# MOTOR_DRV.net
KiCad netlist of a schematic drawn in Altium Designer
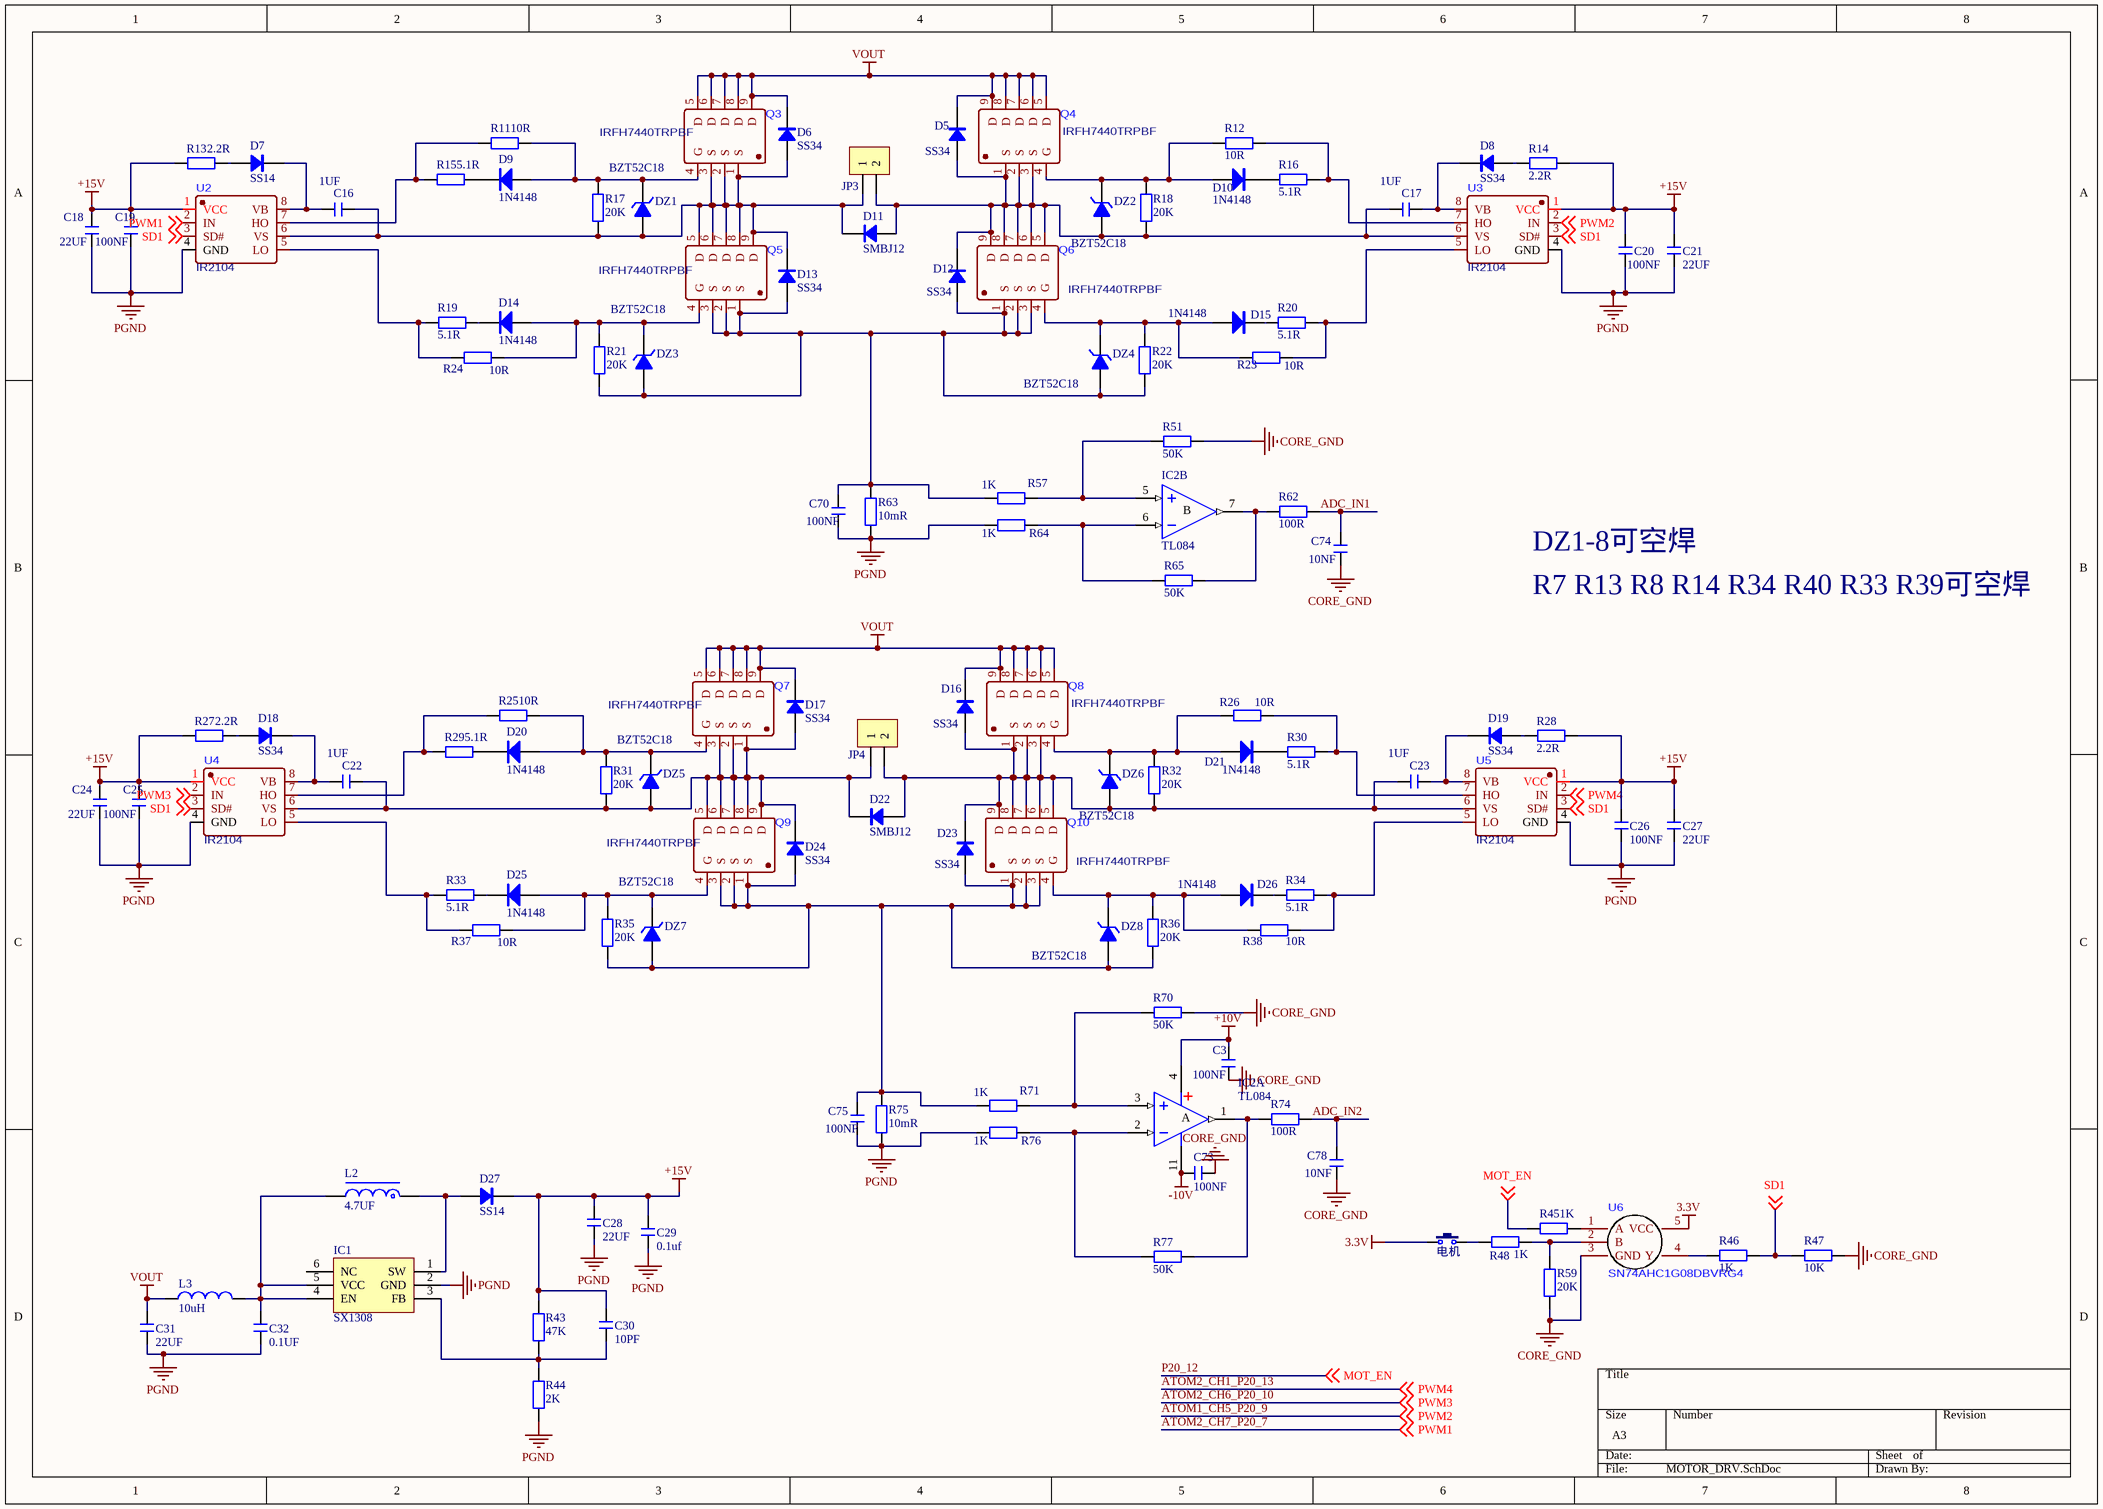
[diagram p0: MOTOR_DRV.SchDoc]

(export (version "E")
  (design (tool "Eeschema 10.0.6"))
  (components
    (comp (ref "C3")
      (value "100NF")
      (footprint "C 0805_L")
      (description "无极性贴片电容")
      (fields (field (name "版权归属") "源创客"))
      (libsource (lib "3.1   - 电阻-电容-电感") (part "C"))
    )
    (comp (ref "C16")
      (value "1UF")
      (footprint "C 1206_L")
      (description "无极性贴片电容")
      (fields (field (name "版权归属") "源创客"))
      (libsource (lib "3.1   - 电阻-电容-电感") (part "C"))
    )
    (comp (ref "C17")
      (value "1UF")
      (footprint "C 1206_L")
      (description "无极性贴片电容")
      (fields (field (name "版权归属") "源创客"))
      (libsource (lib "3.1   - 电阻-电容-电感") (part "C"))
    )
    (comp (ref "C18")
      (value "22UF")
      (footprint "C 0805_L")
      (description "无极性贴片电容")
      (fields (field (name "版权归属") "源创客"))
      (libsource (lib "3.1   - 电阻-电容-电感") (part "C"))
    )
    (comp (ref "C19")
      (value "100NF")
      (footprint "C 0805_L")
      (description "无极性贴片电容")
      (fields (field (name "版权归属") "源创客"))
      (libsource (lib "3.1   - 电阻-电容-电感") (part "C"))
    )
    (comp (ref "C20")
      (value "100NF")
      (footprint "C 0805_L")
      (description "无极性贴片电容")
      (fields (field (name "版权归属") "源创客"))
      (libsource (lib "3.1   - 电阻-电容-电感") (part "C"))
    )
    (comp (ref "C21")
      (value "22UF")
      (footprint "C 0805_L")
      (description "无极性贴片电容")
      (fields (field (name "版权归属") "源创客"))
      (libsource (lib "3.1   - 电阻-电容-电感") (part "C"))
    )
    (comp (ref "C22")
      (value "1UF")
      (footprint "C 1206_L")
      (description "无极性贴片电容")
      (fields (field (name "版权归属") "源创客"))
      (libsource (lib "3.1   - 电阻-电容-电感") (part "C"))
    )
    (comp (ref "C23")
      (value "1UF")
      (footprint "C 1206_L")
      (description "无极性贴片电容")
      (fields (field (name "版权归属") "源创客"))
      (libsource (lib "3.1   - 电阻-电容-电感") (part "C"))
    )
    (comp (ref "C24")
      (value "22UF")
      (footprint "C 0805_L")
      (description "无极性贴片电容")
      (fields (field (name "版权归属") "源创客"))
      (libsource (lib "3.1   - 电阻-电容-电感") (part "C"))
    )
    (comp (ref "C25")
      (value "100NF")
      (footprint "C 0805_L")
      (description "无极性贴片电容")
      (fields (field (name "版权归属") "源创客"))
      (libsource (lib "3.1   - 电阻-电容-电感") (part "C"))
    )
    (comp (ref "C26")
      (value "100NF")
      (footprint "C 0805_L")
      (description "无极性贴片电容")
      (fields (field (name "版权归属") "源创客"))
      (libsource (lib "3.1   - 电阻-电容-电感") (part "C"))
    )
    (comp (ref "C27")
      (value "22UF")
      (footprint "C 0805_L")
      (description "无极性贴片电容")
      (fields (field (name "版权归属") "源创客"))
      (libsource (lib "3.1   - 电阻-电容-电感") (part "C"))
    )
    (comp (ref "C28")
      (value "22UF")
      (footprint "C 1206_L")
      (description "无极性贴片电容")
      (fields (field (name "版权归属") "源创客"))
      (libsource (lib "3.1   - 电阻-电容-电感") (part "C"))
    )
    (comp (ref "C29")
      (value "0.1uf")
      (footprint "C 0805_L")
      (description "无极性贴片电容")
      (fields (field (name "版权归属") "源创客"))
      (libsource (lib "3.1   - 电阻-电容-电感") (part "C"))
    )
    (comp (ref "C30")
      (value "10PF")
      (footprint "C 0603_L")
      (description "无极性贴片电容")
      (fields (field (name "版权归属") "源创客"))
      (libsource (lib "3.1   - 电阻-电容-电感") (part "C"))
    )
    (comp (ref "C31")
      (value "22UF")
      (footprint "C 1206_L")
      (description "无极性贴片电容")
      (fields (field (name "版权归属") "源创客"))
      (libsource (lib "3.1   - 电阻-电容-电感") (part "C"))
    )
    (comp (ref "C32")
      (value "0.1UF")
      (footprint "C 0805_L")
      (description "无极性贴片电容")
      (fields (field (name "版权归属") "源创客"))
      (libsource (lib "3.1   - 电阻-电容-电感") (part "C"))
    )
    (comp (ref "C70")
      (value "100NF")
      (footprint "C 0805_L")
      (description "无极性贴片电容")
      (fields (field (name "版权归属") "源创客"))
      (libsource (lib "3.1   - 电阻-电容-电感") (part "C"))
    )
    (comp (ref "C73")
      (value "100NF")
      (footprint "C 0805_L")
      (description "无极性贴片电容")
      (fields (field (name "版权归属") "源创客"))
      (libsource (lib "3.1   - 电阻-电容-电感") (part "C"))
    )
    (comp (ref "C74")
      (value "10NF")
      (footprint "C 0805_L")
      (description "无极性贴片电容")
      (fields (field (name "版权归属") "源创客"))
      (libsource (lib "3.1   - 电阻-电容-电感") (part "C"))
    )
    (comp (ref "C75")
      (value "100NF")
      (footprint "C 0805_L")
      (description "无极性贴片电容")
      (fields (field (name "版权归属") "源创客"))
      (libsource (lib "3.1   - 电阻-电容-电感") (part "C"))
    )
    (comp (ref "C78")
      (value "10NF")
      (footprint "C 0805_L")
      (description "无极性贴片电容")
      (fields (field (name "版权归属") "源创客"))
      (libsource (lib "3.1   - 电阻-电容-电感") (part "C"))
    )
    (comp (ref "D5")
      (value "SS34")
      (footprint "SMA")
      (description "肖特基二极管")
      (fields (field (name "版权归属") "源创客"))
      (libsource (lib "8.1   - 二极管-整流桥") (part "SS34"))
    )
    (comp (ref "D6")
      (value "SS34")
      (footprint "SMA")
      (description "肖特基二极管")
      (fields (field (name "版权归属") "源创客"))
      (libsource (lib "8.1   - 二极管-整流桥") (part "SS34"))
    )
    (comp (ref "D7")
      (value "SS14")
      (footprint "SOD-123")
      (description "肖特基二极管")
      (fields (field (name "版权归属") "源创客"))
      (libsource (lib "8.1   - 二极管-整流桥") (part "SS34"))
    )
    (comp (ref "D8")
      (value "SS34")
      (footprint "SOD-123")
      (description "肖特基二极管")
      (fields (field (name "版权归属") "源创客"))
      (libsource (lib "8.1   - 二极管-整流桥") (part "SS34"))
    )
    (comp (ref "D9")
      (value "1N4148")
      (footprint "SOD-323")
      (description "高速开关二极管")
      (fields (field (name "版权归属") "源创客"))
      (libsource (lib "8.1   - 二极管-整流桥") (part "1N4148"))
    )
    (comp (ref "D10")
      (value "1N4148")
      (footprint "SOD-323")
      (description "高速开关二极管")
      (fields (field (name "版权归属") "源创客"))
      (libsource (lib "8.1   - 二极管-整流桥") (part "1N4148"))
    )
    (comp (ref "D11")
      (value "SMBJ12")
      (footprint "SMA")
      (description "肖特基二极管")
      (fields (field (name "版权归属") "源创客"))
      (libsource (lib "8.1   - 二极管-整流桥") (part "SS34"))
    )
    (comp (ref "D12")
      (value "SS34")
      (footprint "SMA")
      (description "肖特基二极管")
      (fields (field (name "版权归属") "源创客"))
      (libsource (lib "8.1   - 二极管-整流桥") (part "SS34"))
    )
    (comp (ref "D13")
      (value "SS34")
      (footprint "SMA")
      (description "肖特基二极管")
      (fields (field (name "版权归属") "源创客"))
      (libsource (lib "8.1   - 二极管-整流桥") (part "SS34"))
    )
    (comp (ref "D14")
      (value "1N4148")
      (footprint "SOD-323")
      (description "高速开关二极管")
      (fields (field (name "版权归属") "源创客"))
      (libsource (lib "8.1   - 二极管-整流桥") (part "1N4148"))
    )
    (comp (ref "D15")
      (value "1N4148")
      (footprint "SOD-323")
      (description "高速开关二极管")
      (fields (field (name "版权归属") "源创客"))
      (libsource (lib "8.1   - 二极管-整流桥") (part "1N4148"))
    )
    (comp (ref "D16")
      (value "SS34")
      (footprint "SMA")
      (description "肖特基二极管")
      (fields (field (name "版权归属") "源创客"))
      (libsource (lib "8.1   - 二极管-整流桥") (part "SS34"))
    )
    (comp (ref "D17")
      (value "SS34")
      (footprint "SMA")
      (description "肖特基二极管")
      (fields (field (name "版权归属") "源创客"))
      (libsource (lib "8.1   - 二极管-整流桥") (part "SS34"))
    )
    (comp (ref "D18")
      (value "SS34")
      (footprint "SOD-123")
      (description "肖特基二极管")
      (fields (field (name "版权归属") "源创客"))
      (libsource (lib "8.1   - 二极管-整流桥") (part "SS34"))
    )
    (comp (ref "D19")
      (value "SS34")
      (footprint "SOD-123")
      (description "肖特基二极管")
      (fields (field (name "版权归属") "源创客"))
      (libsource (lib "8.1   - 二极管-整流桥") (part "SS34"))
    )
    (comp (ref "D20")
      (value "1N4148")
      (footprint "SOD-323")
      (description "高速开关二极管")
      (fields (field (name "版权归属") "源创客"))
      (libsource (lib "8.1   - 二极管-整流桥") (part "1N4148"))
    )
    (comp (ref "D21")
      (value "1N4148")
      (footprint "SOD-323")
      (description "高速开关二极管")
      (fields (field (name "版权归属") "源创客"))
      (libsource (lib "8.1   - 二极管-整流桥") (part "1N4148"))
    )
    (comp (ref "D22")
      (value "SMBJ12")
      (footprint "SMA")
      (description "肖特基二极管")
      (fields (field (name "版权归属") "源创客"))
      (libsource (lib "8.1   - 二极管-整流桥") (part "SS34"))
    )
    (comp (ref "D23")
      (value "SS34")
      (footprint "SMA")
      (description "肖特基二极管")
      (fields (field (name "版权归属") "源创客"))
      (libsource (lib "8.1   - 二极管-整流桥") (part "SS34"))
    )
    (comp (ref "D24")
      (value "SS34")
      (footprint "SMA")
      (description "肖特基二极管")
      (fields (field (name "版权归属") "源创客"))
      (libsource (lib "8.1   - 二极管-整流桥") (part "SS34"))
    )
    (comp (ref "D25")
      (value "1N4148")
      (footprint "SOD-323")
      (description "高速开关二极管")
      (fields (field (name "版权归属") "源创客"))
      (libsource (lib "8.1   - 二极管-整流桥") (part "1N4148"))
    )
    (comp (ref "D26")
      (value "1N4148")
      (footprint "SOD-323")
      (description "高速开关二极管")
      (fields (field (name "版权归属") "源创客"))
      (libsource (lib "8.1   - 二极管-整流桥") (part "1N4148"))
    )
    (comp (ref "D27")
      (value "SS14")
      (footprint "SOD-123")
      (description "肖特基二极管")
      (fields (field (name "版权归属") "源创客"))
      (libsource (lib "8.1   - 二极管-整流桥") (part "SS24"))
    )
    (comp (ref "DZ1")
      (value "BZT52C18")
      (footprint "SOD-323")
      (description "18V稳压管")
      (fields (field (name "版权归属") "源创客"))
      (libsource (lib "8.1   - 二极管-整流桥") (part "1N4102"))
    )
    (comp (ref "DZ2")
      (value "BZT52C18")
      (footprint "SOD-323")
      (description "18V稳压管")
      (fields (field (name "版权归属") "源创客"))
      (libsource (lib "8.1   - 二极管-整流桥") (part "1N4102"))
    )
    (comp (ref "DZ3")
      (value "BZT52C18")
      (footprint "SOD-323")
      (description "18V稳压管")
      (fields (field (name "版权归属") "源创客"))
      (libsource (lib "8.1   - 二极管-整流桥") (part "1N4102"))
    )
    (comp (ref "DZ4")
      (value "BZT52C18")
      (footprint "SOD-323")
      (description "18V稳压管")
      (fields (field (name "版权归属") "源创客"))
      (libsource (lib "8.1   - 二极管-整流桥") (part "1N4102"))
    )
    (comp (ref "DZ5")
      (value "BZT52C18")
      (footprint "SOD-323")
      (description "18V稳压管")
      (fields (field (name "版权归属") "源创客"))
      (libsource (lib "8.1   - 二极管-整流桥") (part "1N4102"))
    )
    (comp (ref "DZ6")
      (value "BZT52C18")
      (footprint "SOD-323")
      (description "18V稳压管")
      (fields (field (name "版权归属") "源创客"))
      (libsource (lib "8.1   - 二极管-整流桥") (part "1N4102"))
    )
    (comp (ref "DZ7")
      (value "BZT52C18")
      (footprint "SOD-323")
      (description "18V稳压管")
      (fields (field (name "版权归属") "源创客"))
      (libsource (lib "8.1   - 二极管-整流桥") (part "1N4102"))
    )
    (comp (ref "DZ8")
      (value "BZT52C18")
      (footprint "SOD-323")
      (description "18V稳压管")
      (fields (field (name "版权归属") "源创客"))
      (libsource (lib "8.1   - 二极管-整流桥") (part "1N4102"))
    )
    (comp (ref "IC1")
      (value "SX1308")
      (footprint "SOT23-6N")
      (description "可调升压芯片")
      (fields (field (name "版权归属") "源创客"))
      (libsource (lib "1.3   - 电源类芯片") (part "SX1308"))
    )
    (comp (ref "IC2")
      (value "TL084")
      (footprint "SOP14_N")
      (description "4路运放")
      (fields (field (name "版权归属") "源创客"))
      (libsource (lib "1.5   - 运放-功放") (part "TL084"))
    )
    (comp (ref "JP3")
      (value "HDR-1X2")
      (footprint "KF2EDGK5.08-LI-2P")
      (description "2P接插件")
      (fields (field (name "版权归属") "源创客"))
      (libsource (lib "4.11 - 接插件-脚距5.08") (part "Header 2"))
    )
    (comp (ref "JP4")
      (value "HDR-1X2")
      (footprint "KF2EDGK5.08-LI-2P")
      (description "2P接插件")
      (fields (field (name "版权归属") "源创客"))
      (libsource (lib "4.11 - 接插件-脚距5.08") (part "Header 2"))
    )
    (comp (ref "L2")
      (value "4.7UF")
      (footprint "L-SMD-0420")
      (description "功率屏蔽电感")
      (fields (field (name "版权归属") "源创客"))
      (libsource (lib "3.1   - 电阻-电容-电感") (part "L-CDRH"))
    )
    (comp (ref "L3")
      (value "10uH")
      (footprint "L 0805_L")
      (description "小功率贴片电感")
      (fields (field (name "版权归属") "源创客"))
      (libsource (lib "3.1   - 电阻-电容-电感") (part "L"))
    )
    (comp (ref "Q3")
      (value "IRFH7440TRPBF")
      (footprint "PQFN-8P_L5.8-W4.9-P1.27-LS6.0-BL")
      (libsource (lib "IRFH7440TRPBF") (part "IRFH7440TRPBF"))
    )
    (comp (ref "Q4")
      (value "IRFH7440TRPBF")
      (footprint "PQFN-8P_L5.8-W4.9-P1.27-LS6.0-BL")
      (libsource (lib "IRFH7440TRPBF") (part "IRFH7440TRPBF"))
    )
    (comp (ref "Q5")
      (value "IRFH7440TRPBF")
      (footprint "PQFN-8P_L5.8-W4.9-P1.27-LS6.0-BL")
      (libsource (lib "IRFH7440TRPBF") (part "IRFH7440TRPBF"))
    )
    (comp (ref "Q6")
      (value "IRFH7440TRPBF")
      (footprint "PQFN-8P_L5.8-W4.9-P1.27-LS6.0-BL")
      (libsource (lib "IRFH7440TRPBF") (part "IRFH7440TRPBF"))
    )
    (comp (ref "Q7")
      (value "IRFH7440TRPBF")
      (footprint "PQFN-8P_L5.8-W4.9-P1.27-LS6.0-BL")
      (libsource (lib "IRFH7440TRPBF") (part "IRFH7440TRPBF"))
    )
    (comp (ref "Q8")
      (value "IRFH7440TRPBF")
      (footprint "PQFN-8P_L5.8-W4.9-P1.27-LS6.0-BL")
      (libsource (lib "IRFH7440TRPBF") (part "IRFH7440TRPBF"))
    )
    (comp (ref "Q9")
      (value "IRFH7440TRPBF")
      (footprint "PQFN-8P_L5.8-W4.9-P1.27-LS6.0-BL")
      (libsource (lib "IRFH7440TRPBF") (part "IRFH7440TRPBF"))
    )
    (comp (ref "Q10")
      (value "IRFH7440TRPBF")
      (footprint "PQFN-8P_L5.8-W4.9-P1.27-LS6.0-BL")
      (libsource (lib "IRFH7440TRPBF") (part "IRFH7440TRPBF"))
    )
    (comp (ref "R11")
      (value "10R")
      (footprint "R 0805_L")
      (description "贴片电阻")
      (fields (field (name "版权归属") "源创客"))
      (libsource (lib "3.1   - 电阻-电容-电感") (part "R"))
    )
    (comp (ref "R12")
      (value "10R")
      (footprint "R 0805_L")
      (description "贴片电阻")
      (fields (field (name "版权归属") "源创客"))
      (libsource (lib "3.1   - 电阻-电容-电感") (part "R"))
    )
    (comp (ref "R13")
      (value "2.2R")
      (footprint "R 0805_L")
      (description "贴片电阻")
      (fields (field (name "版权归属") "源创客"))
      (libsource (lib "3.1   - 电阻-电容-电感") (part "R"))
    )
    (comp (ref "R14")
      (value "2.2R")
      (footprint "R 0805_L")
      (description "贴片电阻")
      (fields (field (name "版权归属") "源创客"))
      (libsource (lib "3.1   - 电阻-电容-电感") (part "R"))
    )
    (comp (ref "R15")
      (value "5.1R")
      (footprint "R 0805_L")
      (description "贴片电阻")
      (fields (field (name "版权归属") "源创客"))
      (libsource (lib "3.1   - 电阻-电容-电感") (part "R"))
    )
    (comp (ref "R16")
      (value "5.1R")
      (footprint "R 0805_L")
      (description "贴片电阻")
      (fields (field (name "版权归属") "源创客"))
      (libsource (lib "3.1   - 电阻-电容-电感") (part "R"))
    )
    (comp (ref "R17")
      (value "20K")
      (footprint "R 0805_L")
      (description "贴片电阻")
      (fields (field (name "版权归属") "源创客"))
      (libsource (lib "3.1   - 电阻-电容-电感") (part "R"))
    )
    (comp (ref "R18")
      (value "20K")
      (footprint "R 0805_L")
      (description "贴片电阻")
      (fields (field (name "版权归属") "源创客"))
      (libsource (lib "3.1   - 电阻-电容-电感") (part "R"))
    )
    (comp (ref "R19")
      (value "5.1R")
      (footprint "R 0805_L")
      (description "贴片电阻")
      (fields (field (name "版权归属") "源创客"))
      (libsource (lib "3.1   - 电阻-电容-电感") (part "R"))
    )
    (comp (ref "R20")
      (value "5.1R")
      (footprint "R 0805_L")
      (description "贴片电阻")
      (fields (field (name "版权归属") "源创客"))
      (libsource (lib "3.1   - 电阻-电容-电感") (part "R"))
    )
    (comp (ref "R21")
      (value "20K")
      (footprint "R 0805_L")
      (description "贴片电阻")
      (fields (field (name "版权归属") "源创客"))
      (libsource (lib "3.1   - 电阻-电容-电感") (part "R"))
    )
    (comp (ref "R22")
      (value "20K")
      (footprint "R 0805_L")
      (description "贴片电阻")
      (fields (field (name "版权归属") "源创客"))
      (libsource (lib "3.1   - 电阻-电容-电感") (part "R"))
    )
    (comp (ref "R23")
      (value "10R")
      (footprint "R 0805_L")
      (description "贴片电阻")
      (fields (field (name "版权归属") "源创客"))
      (libsource (lib "3.1   - 电阻-电容-电感") (part "R"))
    )
    (comp (ref "R24")
      (value "10R")
      (footprint "R 0805_L")
      (description "贴片电阻")
      (fields (field (name "版权归属") "源创客"))
      (libsource (lib "3.1   - 电阻-电容-电感") (part "R"))
    )
    (comp (ref "R25")
      (value "10R")
      (footprint "R 0805_L")
      (description "贴片电阻")
      (fields (field (name "版权归属") "源创客"))
      (libsource (lib "3.1   - 电阻-电容-电感") (part "R"))
    )
    (comp (ref "R26")
      (value "10R")
      (footprint "R 0805_L")
      (description "贴片电阻")
      (fields (field (name "版权归属") "源创客"))
      (libsource (lib "3.1   - 电阻-电容-电感") (part "R"))
    )
    (comp (ref "R27")
      (value "2.2R")
      (footprint "R 0805_L")
      (description "贴片电阻")
      (fields (field (name "版权归属") "源创客"))
      (libsource (lib "3.1   - 电阻-电容-电感") (part "R"))
    )
    (comp (ref "R28")
      (value "2.2R")
      (footprint "R 0805_L")
      (description "贴片电阻")
      (fields (field (name "版权归属") "源创客"))
      (libsource (lib "3.1   - 电阻-电容-电感") (part "R"))
    )
    (comp (ref "R29")
      (value "5.1R")
      (footprint "R 0805_L")
      (description "贴片电阻")
      (fields (field (name "版权归属") "源创客"))
      (libsource (lib "3.1   - 电阻-电容-电感") (part "R"))
    )
    (comp (ref "R30")
      (value "5.1R")
      (footprint "R 0805_L")
      (description "贴片电阻")
      (fields (field (name "版权归属") "源创客"))
      (libsource (lib "3.1   - 电阻-电容-电感") (part "R"))
    )
    (comp (ref "R31")
      (value "20K")
      (footprint "R 0805_L")
      (description "贴片电阻")
      (fields (field (name "版权归属") "源创客"))
      (libsource (lib "3.1   - 电阻-电容-电感") (part "R"))
    )
    (comp (ref "R32")
      (value "20K")
      (footprint "R 0805_L")
      (description "贴片电阻")
      (fields (field (name "版权归属") "源创客"))
      (libsource (lib "3.1   - 电阻-电容-电感") (part "R"))
    )
    (comp (ref "R33")
      (value "5.1R")
      (footprint "R 0805_L")
      (description "贴片电阻")
      (fields (field (name "版权归属") "源创客"))
      (libsource (lib "3.1   - 电阻-电容-电感") (part "R"))
    )
    (comp (ref "R34")
      (value "5.1R")
      (footprint "R 0805_L")
      (description "贴片电阻")
      (fields (field (name "版权归属") "源创客"))
      (libsource (lib "3.1   - 电阻-电容-电感") (part "R"))
    )
    (comp (ref "R35")
      (value "20K")
      (footprint "R 0805_L")
      (description "贴片电阻")
      (fields (field (name "版权归属") "源创客"))
      (libsource (lib "3.1   - 电阻-电容-电感") (part "R"))
    )
    (comp (ref "R36")
      (value "20K")
      (footprint "R 0805_L")
      (description "贴片电阻")
      (fields (field (name "版权归属") "源创客"))
      (libsource (lib "3.1   - 电阻-电容-电感") (part "R"))
    )
    (comp (ref "R37")
      (value "10R")
      (footprint "R 0805_L")
      (description "贴片电阻")
      (fields (field (name "版权归属") "源创客"))
      (libsource (lib "3.1   - 电阻-电容-电感") (part "R"))
    )
    (comp (ref "R38")
      (value "10R")
      (footprint "R 0805_L")
      (description "贴片电阻")
      (fields (field (name "版权归属") "源创客"))
      (libsource (lib "3.1   - 电阻-电容-电感") (part "R"))
    )
    (comp (ref "R43")
      (value "47K")
      (footprint "R 0805_L")
      (description "贴片电阻")
      (fields (field (name "版权归属") "源创客"))
      (libsource (lib "3.1   - 电阻-电容-电感") (part "R"))
    )
    (comp (ref "R44")
      (value "2K")
      (footprint "R 0805_L")
      (description "贴片电阻")
      (fields (field (name "版权归属") "源创客"))
      (libsource (lib "3.1   - 电阻-电容-电感") (part "R"))
    )
    (comp (ref "R45")
      (value "1K")
      (footprint "R 0805_L")
      (description "贴片电阻")
      (fields (field (name "版权归属") "源创客"))
      (libsource (lib "3.1   - 电阻-电容-电感") (part "R"))
    )
    (comp (ref "R46")
      (value "1K")
      (footprint "R 0805_L")
      (description "贴片电阻")
      (fields (field (name "版权归属") "源创客"))
      (libsource (lib "3.1   - 电阻-电容-电感") (part "R"))
    )
    (comp (ref "R47")
      (value "10K")
      (footprint "R 0805_L")
      (description "贴片电阻")
      (fields (field (name "版权归属") "源创客"))
      (libsource (lib "3.1   - 电阻-电容-电感") (part "R"))
    )
    (comp (ref "R48")
      (value "1K")
      (footprint "R 0805_L")
      (description "贴片电阻")
      (fields (field (name "版权归属") "源创客"))
      (libsource (lib "3.1   - 电阻-电容-电感") (part "R"))
    )
    (comp (ref "R51")
      (value "50K")
      (footprint "R 0805_L")
      (description "贴片电阻")
      (fields (field (name "版权归属") "源创客"))
      (libsource (lib "3.1   - 电阻-电容-电感") (part "R"))
    )
    (comp (ref "R57")
      (value "1K")
      (footprint "R 0805_L")
      (description "贴片电阻")
      (fields (field (name "版权归属") "源创客"))
      (libsource (lib "3.1   - 电阻-电容-电感") (part "R"))
    )
    (comp (ref "R59")
      (value "20K")
      (footprint "R 0805_L")
      (description "贴片电阻")
      (fields (field (name "版权归属") "源创客"))
      (libsource (lib "3.1   - 电阻-电容-电感") (part "R"))
    )
    (comp (ref "R62")
      (value "100R")
      (footprint "R 0805_L")
      (description "贴片电阻")
      (fields (field (name "版权归属") "源创客"))
      (libsource (lib "3.1   - 电阻-电容-电感") (part "R"))
    )
    (comp (ref "R63")
      (value "10mR")
      (footprint "R 2512_M")
      (description "贴片电阻")
      (fields (field (name "版权归属") "源创客"))
      (libsource (lib "3.1   - 电阻-电容-电感") (part "R"))
    )
    (comp (ref "R64")
      (value "1K")
      (footprint "R 0805_L")
      (description "贴片电阻")
      (fields (field (name "版权归属") "源创客"))
      (libsource (lib "3.1   - 电阻-电容-电感") (part "R"))
    )
    (comp (ref "R65")
      (value "50K")
      (footprint "R 0805_L")
      (description "贴片电阻")
      (fields (field (name "版权归属") "源创客"))
      (libsource (lib "3.1   - 电阻-电容-电感") (part "R"))
    )
    (comp (ref "R70")
      (value "50K")
      (footprint "R 0805_L")
      (description "贴片电阻")
      (fields (field (name "版权归属") "源创客"))
      (libsource (lib "3.1   - 电阻-电容-电感") (part "R"))
    )
    (comp (ref "R71")
      (value "1K")
      (footprint "R 0805_L")
      (description "贴片电阻")
      (fields (field (name "版权归属") "源创客"))
      (libsource (lib "3.1   - 电阻-电容-电感") (part "R"))
    )
    (comp (ref "R74")
      (value "100R")
      (footprint "R 0805_L")
      (description "贴片电阻")
      (fields (field (name "版权归属") "源创客"))
      (libsource (lib "3.1   - 电阻-电容-电感") (part "R"))
    )
    (comp (ref "R75")
      (value "10mR")
      (footprint "R 2512_M")
      (description "贴片电阻")
      (fields (field (name "版权归属") "源创客"))
      (libsource (lib "3.1   - 电阻-电容-电感") (part "R"))
    )
    (comp (ref "R76")
      (value "1K")
      (footprint "R 0805_L")
      (description "贴片电阻")
      (fields (field (name "版权归属") "源创客"))
      (libsource (lib "3.1   - 电阻-电容-电感") (part "R"))
    )
    (comp (ref "R77")
      (value "50K")
      (footprint "R 0805_L")
      (description "贴片电阻")
      (fields (field (name "版权归属") "源创客"))
      (libsource (lib "3.1   - 电阻-电容-电感") (part "R"))
    )
    (comp (ref "U2") (value "IR2104") (footprint "SOP8_M") (libsource (lib "EG2104") (part "EG2104")))
    (comp (ref "U3") (value "IR2104") (footprint "SOP8_M") (libsource (lib "EG2104") (part "EG2104")))
    (comp (ref "U4") (value "IR2104") (footprint "SOP8_M") (libsource (lib "EG2104") (part "EG2104")))
    (comp (ref "U5") (value "IR2104") (footprint "SOP8_M") (libsource (lib "EG2104") (part "EG2104")))
    (comp (ref "U6")
      (value "SN74AHC1G08DBVRG4")
      (footprint "SOT23-5L")
      (libsource (lib "SN74AHC1G08DBVRG4") (part "SN74AHC1G08DBVRG4"))
    )
    (comp (ref "电机")
      (value "6x6x5")
      (footprint "KEY-TH_CN-KCD11")
      (description "2脚直插6x6轻触开关")
      (fields (field (name "版权归属") "源创客"))
      (libsource (lib "5.1   - 按键-开关") (part "TSW DIP-2Pin-6x6"))
    )
  )
  (nets
    (net (code "1") (name "+10V") (class "Default")
      (node (ref "C3") (pin "2") (pinfunction "2_2") (pintype "passive"))
      (node (ref "IC2") (pin "4") (pinfunction "V+_4") (pintype "power_in"))
    )
    (net (code "2") (name "+15V") (class "Default")
      (node (ref "C18") (pin "2") (pinfunction "2_2") (pintype "passive"))
      (node (ref "C19") (pin "2") (pinfunction "2_2") (pintype "passive"))
      (node (ref "C20") (pin "2") (pinfunction "2_2") (pintype "passive"))
      (node (ref "C21") (pin "2") (pinfunction "2_2") (pintype "passive"))
      (node (ref "C24") (pin "2") (pinfunction "2_2") (pintype "passive"))
      (node (ref "C25") (pin "2") (pinfunction "2_2") (pintype "passive"))
      (node (ref "C26") (pin "2") (pinfunction "2_2") (pintype "passive"))
      (node (ref "C27") (pin "2") (pinfunction "2_2") (pintype "passive"))
      (node (ref "C28") (pin "1") (pinfunction "1_1") (pintype "passive"))
      (node (ref "C29") (pin "1") (pinfunction "1_1") (pintype "passive"))
      (node (ref "C30") (pin "1") (pinfunction "1_1") (pintype "passive"))
      (node (ref "D27") (pin "2") (pinfunction "K_2") (pintype "passive"))
      (node (ref "R13") (pin "1") (pinfunction "1_1") (pintype "passive"))
      (node (ref "R14") (pin "1") (pinfunction "1_1") (pintype "passive"))
      (node (ref "R27") (pin "1") (pinfunction "1_1") (pintype "passive"))
      (node (ref "R28") (pin "1") (pinfunction "1_1") (pintype "passive"))
      (node (ref "R43") (pin "1") (pinfunction "1_1") (pintype "passive"))
      (node (ref "U2") (pin "1") (pinfunction "VCC_1") (pintype "passive"))
      (node (ref "U3") (pin "1") (pinfunction "VCC_1") (pintype "passive"))
      (node (ref "U4") (pin "1") (pinfunction "VCC_1") (pintype "passive"))
      (node (ref "U5") (pin "1") (pinfunction "VCC_1") (pintype "passive"))
    )
    (net (code "3") (name "-10V") (class "Default")
      (node (ref "C73") (pin "2") (pinfunction "2_2") (pintype "passive"))
      (node (ref "IC2") (pin "11") (pinfunction "V-_11") (pintype "power_in"))
    )
    (net (code "4") (name "/ADC_IN1") (class "Default")
      (node (ref "C74") (pin "2") (pinfunction "2_2") (pintype "passive"))
      (node (ref "R62") (pin "1") (pinfunction "1_1") (pintype "passive"))
    )
    (net (code "5") (name "/ADC_IN2") (class "Default")
      (node (ref "C78") (pin "2") (pinfunction "2_2") (pintype "passive"))
      (node (ref "R74") (pin "1") (pinfunction "1_1") (pintype "passive"))
    )
    (net (code "6") (name "3.3V") (class "Default")
      (node (ref "U6") (pin "5") (pinfunction "VCC_5") (pintype "passive"))
      (node (ref "电机") (pin "1") (pinfunction "1_1") (pintype "passive"))
    )
    (net (code "7") (name "CORE_GND") (class "Default")
      (node (ref "C3") (pin "1") (pinfunction "1_1") (pintype "passive"))
      (node (ref "C73") (pin "1") (pinfunction "1_1") (pintype "passive"))
      (node (ref "C74") (pin "1") (pinfunction "1_1") (pintype "passive"))
      (node (ref "C78") (pin "1") (pinfunction "1_1") (pintype "passive"))
      (node (ref "R47") (pin "2") (pinfunction "2_2") (pintype "passive"))
      (node (ref "R51") (pin "1") (pinfunction "1_1") (pintype "passive"))
      (node (ref "R59") (pin "2") (pinfunction "2_2") (pintype "passive"))
      (node (ref "R70") (pin "1") (pinfunction "1_1") (pintype "passive"))
      (node (ref "U6") (pin "3") (pinfunction "GND_3") (pintype "passive"))
    )
    (net (code "8") (name "MOT_EN") (class "Default")
      (node (ref "R45") (pin "2") (pinfunction "2_2") (pintype "passive"))
    )
    (net (code "9") (name "Net-(D7-A)") (class "Default")
      (node (ref "D7") (pin "1") (pinfunction "A_1") (pintype "passive"))
      (node (ref "R13") (pin "2") (pinfunction "2_2") (pintype "passive"))
    )
    (net (code "10") (name "Net-(D7-K)") (class "Default")
      (node (ref "C16") (pin "2") (pinfunction "2_2") (pintype "passive"))
      (node (ref "D7") (pin "2") (pinfunction "K_2") (pintype "passive"))
      (node (ref "U2") (pin "8") (pinfunction "VB_8") (pintype "passive"))
    )
    (net (code "11") (name "Net-(D8-A)") (class "Default")
      (node (ref "D8") (pin "1") (pinfunction "A_1") (pintype "passive"))
      (node (ref "R14") (pin "2") (pinfunction "2_2") (pintype "passive"))
    )
    (net (code "12") (name "Net-(D8-K)") (class "Default")
      (node (ref "C17") (pin "2") (pinfunction "2_2") (pintype "passive"))
      (node (ref "D8") (pin "2") (pinfunction "K_2") (pintype "passive"))
      (node (ref "U3") (pin "8") (pinfunction "VB_8") (pintype "passive"))
    )
    (net (code "13") (name "Net-(D9-A)") (class "Default")
      (node (ref "D9") (pin "1") (pinfunction "A_1") (pintype "passive"))
      (node (ref "DZ1") (pin "2") (pinfunction "K_2") (pintype "passive"))
      (node (ref "Q3") (pin "4") (pinfunction "G_4") (pintype "passive"))
      (node (ref "R11") (pin "2") (pinfunction "2_2") (pintype "passive"))
      (node (ref "R17") (pin "2") (pinfunction "2_2") (pintype "passive"))
    )
    (net (code "14") (name "Net-(D9-K)") (class "Default")
      (node (ref "D9") (pin "2") (pinfunction "K_2") (pintype "passive"))
      (node (ref "R15") (pin "2") (pinfunction "2_2") (pintype "passive"))
    )
    (net (code "15") (name "Net-(D10-A)") (class "Default")
      (node (ref "D10") (pin "1") (pinfunction "A_1") (pintype "passive"))
      (node (ref "DZ2") (pin "2") (pinfunction "K_2") (pintype "passive"))
      (node (ref "Q4") (pin "4") (pinfunction "G_4") (pintype "passive"))
      (node (ref "R12") (pin "2") (pinfunction "2_2") (pintype "passive"))
      (node (ref "R18") (pin "2") (pinfunction "2_2") (pintype "passive"))
    )
    (net (code "16") (name "Net-(D10-K)") (class "Default")
      (node (ref "D10") (pin "2") (pinfunction "K_2") (pintype "passive"))
      (node (ref "R16") (pin "2") (pinfunction "2_2") (pintype "passive"))
    )
    (net (code "17") (name "Net-(D11-A)") (class "Default")
      (node (ref "C17") (pin "1") (pinfunction "1_1") (pintype "passive"))
      (node (ref "D11") (pin "1") (pinfunction "A_1") (pintype "passive"))
      (node (ref "D12") (pin "2") (pinfunction "K_2") (pintype "passive"))
      (node (ref "D5") (pin "1") (pinfunction "A_1") (pintype "passive"))
      (node (ref "DZ2") (pin "1") (pinfunction "A_1") (pintype "passive"))
      (node (ref "JP3") (pin "2") (pinfunction "2_2") (pintype "passive"))
      (node (ref "Q4") (pin "1") (pinfunction "S_1") (pintype "passive"))
      (node (ref "Q4") (pin "2") (pinfunction "S_2") (pintype "passive"))
      (node (ref "Q4") (pin "3") (pinfunction "S_3") (pintype "passive"))
      (node (ref "Q6") (pin "5") (pinfunction "D_5") (pintype "passive"))
      (node (ref "Q6") (pin "6") (pinfunction "D_6") (pintype "passive"))
      (node (ref "Q6") (pin "7") (pinfunction "D_7") (pintype "passive"))
      (node (ref "Q6") (pin "8") (pinfunction "D_8") (pintype "passive"))
      (node (ref "Q6") (pin "9") (pinfunction "D_9") (pintype "passive"))
      (node (ref "R18") (pin "1") (pinfunction "1_1") (pintype "passive"))
      (node (ref "U3") (pin "6") (pinfunction "VS_6") (pintype "passive"))
    )
    (net (code "18") (name "Net-(D11-K)") (class "Default")
      (node (ref "C16") (pin "1") (pinfunction "1_1") (pintype "passive"))
      (node (ref "D11") (pin "2") (pinfunction "K_2") (pintype "passive"))
      (node (ref "D13") (pin "2") (pinfunction "K_2") (pintype "passive"))
      (node (ref "D6") (pin "1") (pinfunction "A_1") (pintype "passive"))
      (node (ref "DZ1") (pin "1") (pinfunction "A_1") (pintype "passive"))
      (node (ref "JP3") (pin "1") (pinfunction "1_1") (pintype "passive"))
      (node (ref "Q3") (pin "1") (pinfunction "S_1") (pintype "passive"))
      (node (ref "Q3") (pin "2") (pinfunction "S_2") (pintype "passive"))
      (node (ref "Q3") (pin "3") (pinfunction "S_3") (pintype "passive"))
      (node (ref "Q5") (pin "5") (pinfunction "D_5") (pintype "passive"))
      (node (ref "Q5") (pin "6") (pinfunction "D_6") (pintype "passive"))
      (node (ref "Q5") (pin "7") (pinfunction "D_7") (pintype "passive"))
      (node (ref "Q5") (pin "8") (pinfunction "D_8") (pintype "passive"))
      (node (ref "Q5") (pin "9") (pinfunction "D_9") (pintype "passive"))
      (node (ref "R17") (pin "1") (pinfunction "1_1") (pintype "passive"))
      (node (ref "U2") (pin "6") (pinfunction "VS_6") (pintype "passive"))
    )
    (net (code "19") (name "Net-(D12-A)") (class "Default")
      (node (ref "C70") (pin "2") (pinfunction "2_2") (pintype "passive"))
      (node (ref "D12") (pin "1") (pinfunction "A_1") (pintype "passive"))
      (node (ref "D13") (pin "1") (pinfunction "A_1") (pintype "passive"))
      (node (ref "DZ3") (pin "1") (pinfunction "A_1") (pintype "passive"))
      (node (ref "DZ4") (pin "1") (pinfunction "A_1") (pintype "passive"))
      (node (ref "Q5") (pin "1") (pinfunction "S_1") (pintype "passive"))
      (node (ref "Q5") (pin "2") (pinfunction "S_2") (pintype "passive"))
      (node (ref "Q5") (pin "3") (pinfunction "S_3") (pintype "passive"))
      (node (ref "Q6") (pin "1") (pinfunction "S_1") (pintype "passive"))
      (node (ref "Q6") (pin "2") (pinfunction "S_2") (pintype "passive"))
      (node (ref "Q6") (pin "3") (pinfunction "S_3") (pintype "passive"))
      (node (ref "R21") (pin "1") (pinfunction "1_1") (pintype "passive"))
      (node (ref "R22") (pin "1") (pinfunction "1_1") (pintype "passive"))
      (node (ref "R57") (pin "2") (pinfunction "2_2") (pintype "passive"))
      (node (ref "R63") (pin "2") (pinfunction "2_2") (pintype "passive"))
    )
    (net (code "20") (name "Net-(D14-A)") (class "Default")
      (node (ref "D14") (pin "1") (pinfunction "A_1") (pintype "passive"))
      (node (ref "DZ3") (pin "2") (pinfunction "K_2") (pintype "passive"))
      (node (ref "Q5") (pin "4") (pinfunction "G_4") (pintype "passive"))
      (node (ref "R21") (pin "2") (pinfunction "2_2") (pintype "passive"))
      (node (ref "R24") (pin "2") (pinfunction "2_2") (pintype "passive"))
    )
    (net (code "21") (name "Net-(D14-K)") (class "Default")
      (node (ref "D14") (pin "2") (pinfunction "K_2") (pintype "passive"))
      (node (ref "R19") (pin "2") (pinfunction "2_2") (pintype "passive"))
    )
    (net (code "22") (name "Net-(D15-A)") (class "Default")
      (node (ref "D15") (pin "1") (pinfunction "A_1") (pintype "passive"))
      (node (ref "DZ4") (pin "2") (pinfunction "K_2") (pintype "passive"))
      (node (ref "Q6") (pin "4") (pinfunction "G_4") (pintype "passive"))
      (node (ref "R22") (pin "2") (pinfunction "2_2") (pintype "passive"))
      (node (ref "R23") (pin "2") (pinfunction "2_2") (pintype "passive"))
    )
    (net (code "23") (name "Net-(D15-K)") (class "Default")
      (node (ref "D15") (pin "2") (pinfunction "K_2") (pintype "passive"))
      (node (ref "R20") (pin "2") (pinfunction "2_2") (pintype "passive"))
    )
    (net (code "24") (name "Net-(D16-A)") (class "Default")
      (node (ref "C23") (pin "1") (pinfunction "1_1") (pintype "passive"))
      (node (ref "D16") (pin "1") (pinfunction "A_1") (pintype "passive"))
      (node (ref "D22") (pin "1") (pinfunction "A_1") (pintype "passive"))
      (node (ref "D23") (pin "2") (pinfunction "K_2") (pintype "passive"))
      (node (ref "DZ6") (pin "1") (pinfunction "A_1") (pintype "passive"))
      (node (ref "JP4") (pin "2") (pinfunction "2_2") (pintype "passive"))
      (node (ref "Q10") (pin "5") (pinfunction "D_5") (pintype "passive"))
      (node (ref "Q10") (pin "6") (pinfunction "D_6") (pintype "passive"))
      (node (ref "Q10") (pin "7") (pinfunction "D_7") (pintype "passive"))
      (node (ref "Q10") (pin "8") (pinfunction "D_8") (pintype "passive"))
      (node (ref "Q10") (pin "9") (pinfunction "D_9") (pintype "passive"))
      (node (ref "Q8") (pin "1") (pinfunction "S_1") (pintype "passive"))
      (node (ref "Q8") (pin "2") (pinfunction "S_2") (pintype "passive"))
      (node (ref "Q8") (pin "3") (pinfunction "S_3") (pintype "passive"))
      (node (ref "R32") (pin "1") (pinfunction "1_1") (pintype "passive"))
      (node (ref "U5") (pin "6") (pinfunction "VS_6") (pintype "passive"))
    )
    (net (code "25") (name "Net-(D17-A)") (class "Default")
      (node (ref "C22") (pin "1") (pinfunction "1_1") (pintype "passive"))
      (node (ref "D17") (pin "1") (pinfunction "A_1") (pintype "passive"))
      (node (ref "D22") (pin "2") (pinfunction "K_2") (pintype "passive"))
      (node (ref "D24") (pin "2") (pinfunction "K_2") (pintype "passive"))
      (node (ref "DZ5") (pin "1") (pinfunction "A_1") (pintype "passive"))
      (node (ref "JP4") (pin "1") (pinfunction "1_1") (pintype "passive"))
      (node (ref "Q7") (pin "1") (pinfunction "S_1") (pintype "passive"))
      (node (ref "Q7") (pin "2") (pinfunction "S_2") (pintype "passive"))
      (node (ref "Q7") (pin "3") (pinfunction "S_3") (pintype "passive"))
      (node (ref "Q9") (pin "5") (pinfunction "D_5") (pintype "passive"))
      (node (ref "Q9") (pin "6") (pinfunction "D_6") (pintype "passive"))
      (node (ref "Q9") (pin "7") (pinfunction "D_7") (pintype "passive"))
      (node (ref "Q9") (pin "8") (pinfunction "D_8") (pintype "passive"))
      (node (ref "Q9") (pin "9") (pinfunction "D_9") (pintype "passive"))
      (node (ref "R31") (pin "1") (pinfunction "1_1") (pintype "passive"))
      (node (ref "U4") (pin "6") (pinfunction "VS_6") (pintype "passive"))
    )
    (net (code "26") (name "Net-(D18-A)") (class "Default")
      (node (ref "D18") (pin "1") (pinfunction "A_1") (pintype "passive"))
      (node (ref "R27") (pin "2") (pinfunction "2_2") (pintype "passive"))
    )
    (net (code "27") (name "Net-(D18-K)") (class "Default")
      (node (ref "C22") (pin "2") (pinfunction "2_2") (pintype "passive"))
      (node (ref "D18") (pin "2") (pinfunction "K_2") (pintype "passive"))
      (node (ref "U4") (pin "8") (pinfunction "VB_8") (pintype "passive"))
    )
    (net (code "28") (name "Net-(D19-A)") (class "Default")
      (node (ref "D19") (pin "1") (pinfunction "A_1") (pintype "passive"))
      (node (ref "R28") (pin "2") (pinfunction "2_2") (pintype "passive"))
    )
    (net (code "29") (name "Net-(D19-K)") (class "Default")
      (node (ref "C23") (pin "2") (pinfunction "2_2") (pintype "passive"))
      (node (ref "D19") (pin "2") (pinfunction "K_2") (pintype "passive"))
      (node (ref "U5") (pin "8") (pinfunction "VB_8") (pintype "passive"))
    )
    (net (code "30") (name "Net-(D20-A)") (class "Default")
      (node (ref "D20") (pin "1") (pinfunction "A_1") (pintype "passive"))
      (node (ref "DZ5") (pin "2") (pinfunction "K_2") (pintype "passive"))
      (node (ref "Q7") (pin "4") (pinfunction "G_4") (pintype "passive"))
      (node (ref "R25") (pin "2") (pinfunction "2_2") (pintype "passive"))
      (node (ref "R31") (pin "2") (pinfunction "2_2") (pintype "passive"))
    )
    (net (code "31") (name "Net-(D20-K)") (class "Default")
      (node (ref "D20") (pin "2") (pinfunction "K_2") (pintype "passive"))
      (node (ref "R29") (pin "2") (pinfunction "2_2") (pintype "passive"))
    )
    (net (code "32") (name "Net-(D21-A)") (class "Default")
      (node (ref "D21") (pin "1") (pinfunction "A_1") (pintype "passive"))
      (node (ref "DZ6") (pin "2") (pinfunction "K_2") (pintype "passive"))
      (node (ref "Q8") (pin "4") (pinfunction "G_4") (pintype "passive"))
      (node (ref "R26") (pin "2") (pinfunction "2_2") (pintype "passive"))
      (node (ref "R32") (pin "2") (pinfunction "2_2") (pintype "passive"))
    )
    (net (code "33") (name "Net-(D21-K)") (class "Default")
      (node (ref "D21") (pin "2") (pinfunction "K_2") (pintype "passive"))
      (node (ref "R30") (pin "2") (pinfunction "2_2") (pintype "passive"))
    )
    (net (code "34") (name "Net-(D23-A)") (class "Default")
      (node (ref "C75") (pin "2") (pinfunction "2_2") (pintype "passive"))
      (node (ref "D23") (pin "1") (pinfunction "A_1") (pintype "passive"))
      (node (ref "D24") (pin "1") (pinfunction "A_1") (pintype "passive"))
      (node (ref "DZ7") (pin "1") (pinfunction "A_1") (pintype "passive"))
      (node (ref "DZ8") (pin "1") (pinfunction "A_1") (pintype "passive"))
      (node (ref "Q10") (pin "1") (pinfunction "S_1") (pintype "passive"))
      (node (ref "Q10") (pin "2") (pinfunction "S_2") (pintype "passive"))
      (node (ref "Q10") (pin "3") (pinfunction "S_3") (pintype "passive"))
      (node (ref "Q9") (pin "1") (pinfunction "S_1") (pintype "passive"))
      (node (ref "Q9") (pin "2") (pinfunction "S_2") (pintype "passive"))
      (node (ref "Q9") (pin "3") (pinfunction "S_3") (pintype "passive"))
      (node (ref "R35") (pin "1") (pinfunction "1_1") (pintype "passive"))
      (node (ref "R36") (pin "1") (pinfunction "1_1") (pintype "passive"))
      (node (ref "R71") (pin "2") (pinfunction "2_2") (pintype "passive"))
      (node (ref "R75") (pin "2") (pinfunction "2_2") (pintype "passive"))
    )
    (net (code "35") (name "Net-(D25-A)") (class "Default")
      (node (ref "D25") (pin "1") (pinfunction "A_1") (pintype "passive"))
      (node (ref "DZ7") (pin "2") (pinfunction "K_2") (pintype "passive"))
      (node (ref "Q9") (pin "4") (pinfunction "G_4") (pintype "passive"))
      (node (ref "R35") (pin "2") (pinfunction "2_2") (pintype "passive"))
      (node (ref "R37") (pin "2") (pinfunction "2_2") (pintype "passive"))
    )
    (net (code "36") (name "Net-(D25-K)") (class "Default")
      (node (ref "D25") (pin "2") (pinfunction "K_2") (pintype "passive"))
      (node (ref "R33") (pin "2") (pinfunction "2_2") (pintype "passive"))
    )
    (net (code "37") (name "Net-(D26-A)") (class "Default")
      (node (ref "D26") (pin "1") (pinfunction "A_1") (pintype "passive"))
      (node (ref "DZ8") (pin "2") (pinfunction "K_2") (pintype "passive"))
      (node (ref "Q10") (pin "4") (pinfunction "G_4") (pintype "passive"))
      (node (ref "R36") (pin "2") (pinfunction "2_2") (pintype "passive"))
      (node (ref "R38") (pin "2") (pinfunction "2_2") (pintype "passive"))
    )
    (net (code "38") (name "Net-(D26-K)") (class "Default")
      (node (ref "D26") (pin "2") (pinfunction "K_2") (pintype "passive"))
      (node (ref "R34") (pin "2") (pinfunction "2_2") (pintype "passive"))
    )
    (net (code "39") (name "Net-(D27-A)") (class "Default")
      (node (ref "D27") (pin "1") (pinfunction "A_1") (pintype "passive"))
      (node (ref "IC1") (pin "1") (pinfunction "SW_1") (pintype "passive"))
      (node (ref "L2") (pin "1") (pinfunction "1_1") (pintype "passive"))
    )
    (net (code "40") (name "Net-(IC1-EN)") (class "Default")
      (node (ref "C32") (pin "1") (pinfunction "1_1") (pintype "passive"))
      (node (ref "IC1") (pin "4") (pinfunction "EN_4") (pintype "passive"))
      (node (ref "IC1") (pin "5") (pinfunction "VCC_5") (pintype "passive"))
      (node (ref "L2") (pin "2") (pinfunction "2_2") (pintype "passive"))
      (node (ref "L3") (pin "2") (pinfunction "2_2") (pintype "passive"))
    )
    (net (code "41") (name "Net-(IC1-FB)") (class "Default")
      (node (ref "C30") (pin "2") (pinfunction "2_2") (pintype "passive"))
      (node (ref "IC1") (pin "3") (pinfunction "FB_3") (pintype "passive"))
      (node (ref "R43") (pin "2") (pinfunction "2_2") (pintype "passive"))
      (node (ref "R44") (pin "1") (pinfunction "1_1") (pintype "passive"))
    )
    (net (code "42") (name "Net-(IC2A-IN+)") (class "Default")
      (node (ref "IC2") (pin "3") (pinfunction "IN+_3") (pintype "input"))
      (node (ref "R70") (pin "2") (pinfunction "2_2") (pintype "passive"))
      (node (ref "R71") (pin "1") (pinfunction "1_1") (pintype "passive"))
    )
    (net (code "43") (name "Net-(IC2A-IN-)") (class "Default")
      (node (ref "IC2") (pin "2") (pinfunction "IN-_2") (pintype "input"))
      (node (ref "R76") (pin "1") (pinfunction "1_1") (pintype "passive"))
      (node (ref "R77") (pin "2") (pinfunction "2_2") (pintype "passive"))
    )
    (net (code "44") (name "Net-(IC2A-OUT)") (class "Default")
      (node (ref "IC2") (pin "1") (pinfunction "OUT_1") (pintype "output"))
      (node (ref "R74") (pin "2") (pinfunction "2_2") (pintype "passive"))
      (node (ref "R77") (pin "1") (pinfunction "1_1") (pintype "passive"))
    )
    (net (code "45") (name "Net-(IC2B-IN+)") (class "Default")
      (node (ref "IC2") (pin "5") (pinfunction "IN+_5") (pintype "input"))
      (node (ref "R51") (pin "2") (pinfunction "2_2") (pintype "passive"))
      (node (ref "R57") (pin "1") (pinfunction "1_1") (pintype "passive"))
    )
    (net (code "46") (name "Net-(IC2B-IN-)") (class "Default")
      (node (ref "IC2") (pin "6") (pinfunction "IN-_6") (pintype "input"))
      (node (ref "R64") (pin "1") (pinfunction "1_1") (pintype "passive"))
      (node (ref "R65") (pin "2") (pinfunction "2_2") (pintype "passive"))
    )
    (net (code "47") (name "Net-(IC2B-OUT)") (class "Default")
      (node (ref "IC2") (pin "7") (pinfunction "OUT_7") (pintype "output"))
      (node (ref "R62") (pin "2") (pinfunction "2_2") (pintype "passive"))
      (node (ref "R65") (pin "1") (pinfunction "1_1") (pintype "passive"))
    )
    (net (code "48") (name "Net-(R48-Pad2)") (class "Default")
      (node (ref "R48") (pin "2") (pinfunction "2_2") (pintype "passive"))
      (node (ref "电机") (pin "2") (pinfunction "2_2") (pintype "passive"))
    )
    (net (code "49") (name "Net-(U2-HO)") (class "Default")
      (node (ref "R11") (pin "1") (pinfunction "1_1") (pintype "passive"))
      (node (ref "R15") (pin "1") (pinfunction "1_1") (pintype "passive"))
      (node (ref "U2") (pin "7") (pinfunction "HO_7") (pintype "passive"))
    )
    (net (code "50") (name "Net-(U2-LO)") (class "Default")
      (node (ref "R19") (pin "1") (pinfunction "1_1") (pintype "passive"))
      (node (ref "R24") (pin "1") (pinfunction "1_1") (pintype "passive"))
      (node (ref "U2") (pin "5") (pinfunction "LO_5") (pintype "passive"))
    )
    (net (code "51") (name "Net-(U3-HO)") (class "Default")
      (node (ref "R12") (pin "1") (pinfunction "1_1") (pintype "passive"))
      (node (ref "R16") (pin "1") (pinfunction "1_1") (pintype "passive"))
      (node (ref "U3") (pin "7") (pinfunction "HO_7") (pintype "passive"))
    )
    (net (code "52") (name "Net-(U3-LO)") (class "Default")
      (node (ref "R20") (pin "1") (pinfunction "1_1") (pintype "passive"))
      (node (ref "R23") (pin "1") (pinfunction "1_1") (pintype "passive"))
      (node (ref "U3") (pin "5") (pinfunction "LO_5") (pintype "passive"))
    )
    (net (code "53") (name "Net-(U4-HO)") (class "Default")
      (node (ref "R25") (pin "1") (pinfunction "1_1") (pintype "passive"))
      (node (ref "R29") (pin "1") (pinfunction "1_1") (pintype "passive"))
      (node (ref "U4") (pin "7") (pinfunction "HO_7") (pintype "passive"))
    )
    (net (code "54") (name "Net-(U4-LO)") (class "Default")
      (node (ref "R33") (pin "1") (pinfunction "1_1") (pintype "passive"))
      (node (ref "R37") (pin "1") (pinfunction "1_1") (pintype "passive"))
      (node (ref "U4") (pin "5") (pinfunction "LO_5") (pintype "passive"))
    )
    (net (code "55") (name "Net-(U5-HO)") (class "Default")
      (node (ref "R26") (pin "1") (pinfunction "1_1") (pintype "passive"))
      (node (ref "R30") (pin "1") (pinfunction "1_1") (pintype "passive"))
      (node (ref "U5") (pin "7") (pinfunction "HO_7") (pintype "passive"))
    )
    (net (code "56") (name "Net-(U5-LO)") (class "Default")
      (node (ref "R34") (pin "1") (pinfunction "1_1") (pintype "passive"))
      (node (ref "R38") (pin "1") (pinfunction "1_1") (pintype "passive"))
      (node (ref "U5") (pin "5") (pinfunction "LO_5") (pintype "passive"))
    )
    (net (code "57") (name "Net-(U6-A)") (class "Default")
      (node (ref "R45") (pin "1") (pinfunction "1_1") (pintype "passive"))
      (node (ref "U6") (pin "1") (pinfunction "A_1") (pintype "passive"))
    )
    (net (code "58") (name "Net-(U6-B)") (class "Default")
      (node (ref "R48") (pin "1") (pinfunction "1_1") (pintype "passive"))
      (node (ref "R59") (pin "1") (pinfunction "1_1") (pintype "passive"))
      (node (ref "U6") (pin "2") (pinfunction "B_2") (pintype "passive"))
    )
    (net (code "59") (name "Net-(U6-Y)") (class "Default")
      (node (ref "R46") (pin "1") (pinfunction "1_1") (pintype "passive"))
      (node (ref "U6") (pin "4") (pinfunction "Y_4") (pintype "passive"))
    )
    (net (code "60") (name "PGND") (class "Default")
      (node (ref "C18") (pin "1") (pinfunction "1_1") (pintype "passive"))
      (node (ref "C19") (pin "1") (pinfunction "1_1") (pintype "passive"))
      (node (ref "C20") (pin "1") (pinfunction "1_1") (pintype "passive"))
      (node (ref "C21") (pin "1") (pinfunction "1_1") (pintype "passive"))
      (node (ref "C24") (pin "1") (pinfunction "1_1") (pintype "passive"))
      (node (ref "C25") (pin "1") (pinfunction "1_1") (pintype "passive"))
      (node (ref "C26") (pin "1") (pinfunction "1_1") (pintype "passive"))
      (node (ref "C27") (pin "1") (pinfunction "1_1") (pintype "passive"))
      (node (ref "C28") (pin "2") (pinfunction "2_2") (pintype "passive"))
      (node (ref "C29") (pin "2") (pinfunction "2_2") (pintype "passive"))
      (node (ref "C31") (pin "2") (pinfunction "2_2") (pintype "passive"))
      (node (ref "C32") (pin "2") (pinfunction "2_2") (pintype "passive"))
      (node (ref "C70") (pin "1") (pinfunction "1_1") (pintype "passive"))
      (node (ref "C75") (pin "1") (pinfunction "1_1") (pintype "passive"))
      (node (ref "IC1") (pin "2") (pinfunction "GND_2") (pintype "passive"))
      (node (ref "R44") (pin "2") (pinfunction "2_2") (pintype "passive"))
      (node (ref "R63") (pin "1") (pinfunction "1_1") (pintype "passive"))
      (node (ref "R64") (pin "2") (pinfunction "2_2") (pintype "passive"))
      (node (ref "R75") (pin "1") (pinfunction "1_1") (pintype "passive"))
      (node (ref "R76") (pin "2") (pinfunction "2_2") (pintype "passive"))
      (node (ref "U2") (pin "4") (pinfunction "GND_4") (pintype "passive"))
      (node (ref "U3") (pin "4") (pinfunction "GND_4") (pintype "passive"))
      (node (ref "U4") (pin "4") (pinfunction "GND_4") (pintype "passive"))
      (node (ref "U5") (pin "4") (pinfunction "GND_4") (pintype "passive"))
    )
    (net (code "61") (name "PWM1") (class "Default")
      (node (ref "U2") (pin "2") (pinfunction "IN_2") (pintype "passive"))
    )
    (net (code "62") (name "PWM2") (class "Default")
      (node (ref "U3") (pin "2") (pinfunction "IN_2") (pintype "passive"))
    )
    (net (code "63") (name "PWM3") (class "Default")
      (node (ref "U4") (pin "2") (pinfunction "IN_2") (pintype "passive"))
    )
    (net (code "64") (name "PWM4") (class "Default")
      (node (ref "U5") (pin "2") (pinfunction "IN_2") (pintype "passive"))
    )
    (net (code "65") (name "SD1") (class "Default")
      (node (ref "R46") (pin "2") (pinfunction "2_2") (pintype "passive"))
      (node (ref "R47") (pin "1") (pinfunction "1_1") (pintype "passive"))
      (node (ref "U2") (pin "3") (pinfunction "SD#_3") (pintype "passive"))
      (node (ref "U3") (pin "3") (pinfunction "SD#_3") (pintype "passive"))
      (node (ref "U4") (pin "3") (pinfunction "SD#_3") (pintype "passive"))
      (node (ref "U5") (pin "3") (pinfunction "SD#_3") (pintype "passive"))
    )
    (net (code "66") (name "VOUT") (class "Default")
      (node (ref "C31") (pin "1") (pinfunction "1_1") (pintype "passive"))
      (node (ref "D16") (pin "2") (pinfunction "K_2") (pintype "passive"))
      (node (ref "D17") (pin "2") (pinfunction "K_2") (pintype "passive"))
      (node (ref "D5") (pin "2") (pinfunction "K_2") (pintype "passive"))
      (node (ref "D6") (pin "2") (pinfunction "K_2") (pintype "passive"))
      (node (ref "L3") (pin "1") (pinfunction "1_1") (pintype "passive"))
      (node (ref "Q3") (pin "5") (pinfunction "D_5") (pintype "passive"))
      (node (ref "Q3") (pin "6") (pinfunction "D_6") (pintype "passive"))
      (node (ref "Q3") (pin "7") (pinfunction "D_7") (pintype "passive"))
      (node (ref "Q3") (pin "8") (pinfunction "D_8") (pintype "passive"))
      (node (ref "Q3") (pin "9") (pinfunction "D_9") (pintype "passive"))
      (node (ref "Q4") (pin "5") (pinfunction "D_5") (pintype "passive"))
      (node (ref "Q4") (pin "6") (pinfunction "D_6") (pintype "passive"))
      (node (ref "Q4") (pin "7") (pinfunction "D_7") (pintype "passive"))
      (node (ref "Q4") (pin "8") (pinfunction "D_8") (pintype "passive"))
      (node (ref "Q4") (pin "9") (pinfunction "D_9") (pintype "passive"))
      (node (ref "Q7") (pin "5") (pinfunction "D_5") (pintype "passive"))
      (node (ref "Q7") (pin "6") (pinfunction "D_6") (pintype "passive"))
      (node (ref "Q7") (pin "7") (pinfunction "D_7") (pintype "passive"))
      (node (ref "Q7") (pin "8") (pinfunction "D_8") (pintype "passive"))
      (node (ref "Q7") (pin "9") (pinfunction "D_9") (pintype "passive"))
      (node (ref "Q8") (pin "5") (pinfunction "D_5") (pintype "passive"))
      (node (ref "Q8") (pin "6") (pinfunction "D_6") (pintype "passive"))
      (node (ref "Q8") (pin "7") (pinfunction "D_7") (pintype "passive"))
      (node (ref "Q8") (pin "8") (pinfunction "D_8") (pintype "passive"))
      (node (ref "Q8") (pin "9") (pinfunction "D_9") (pintype "passive"))
    )
    (net (code "67") (name "unconnected-(IC1-NC-Pad6)") (class "Default")
      (node (ref "IC1") (pin "6") (pinfunction "NC_6") (pintype "passive"))
    )
  )
)
